# schematic.net
KiCad netlist of a schematic drawn in EAGLE
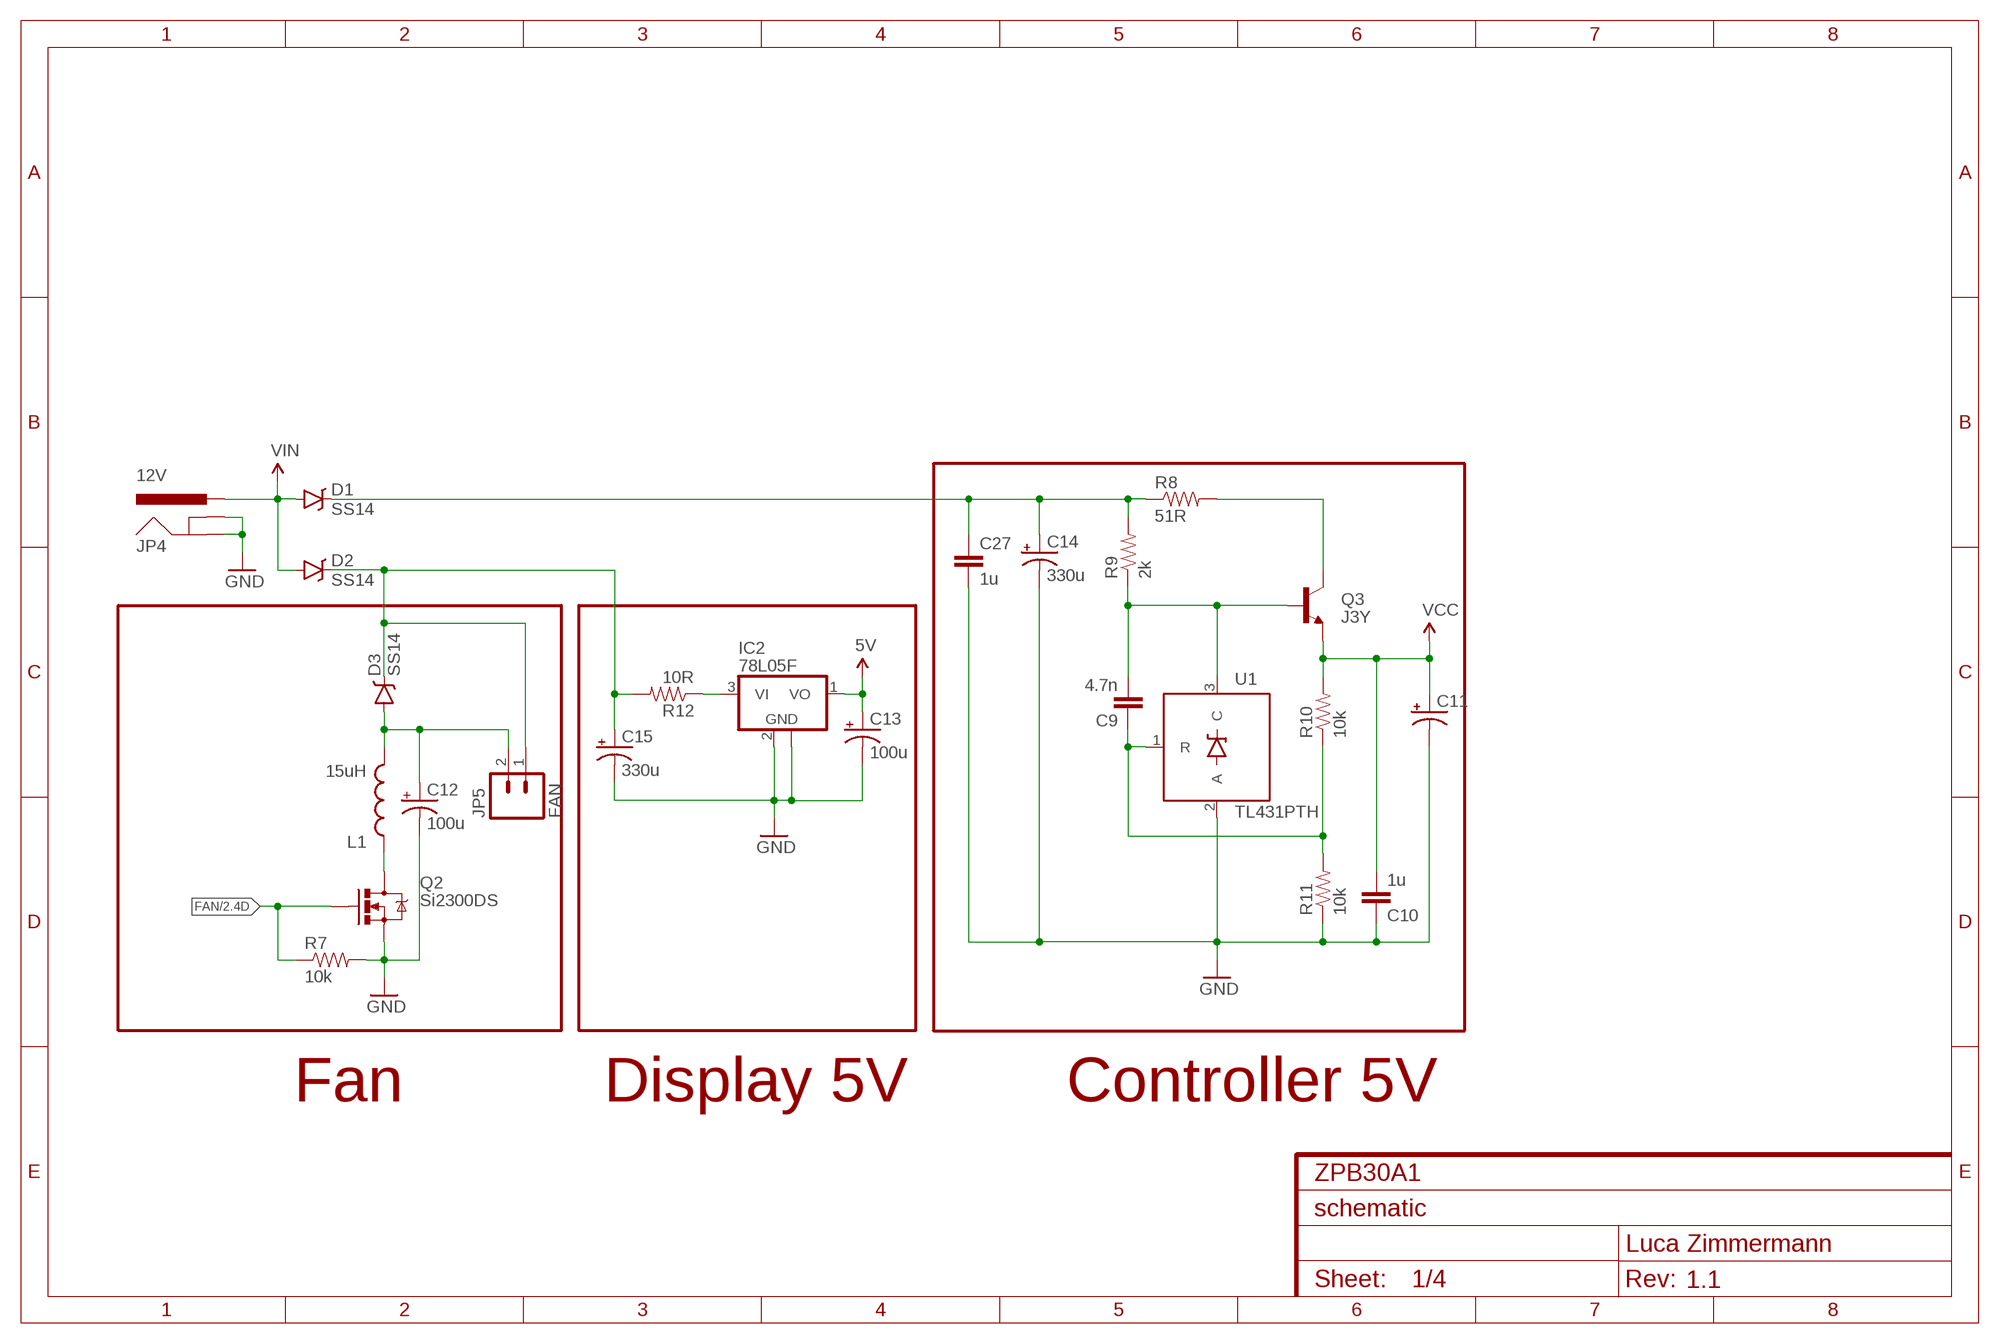
[diagram p0: schematic, sheet 1]
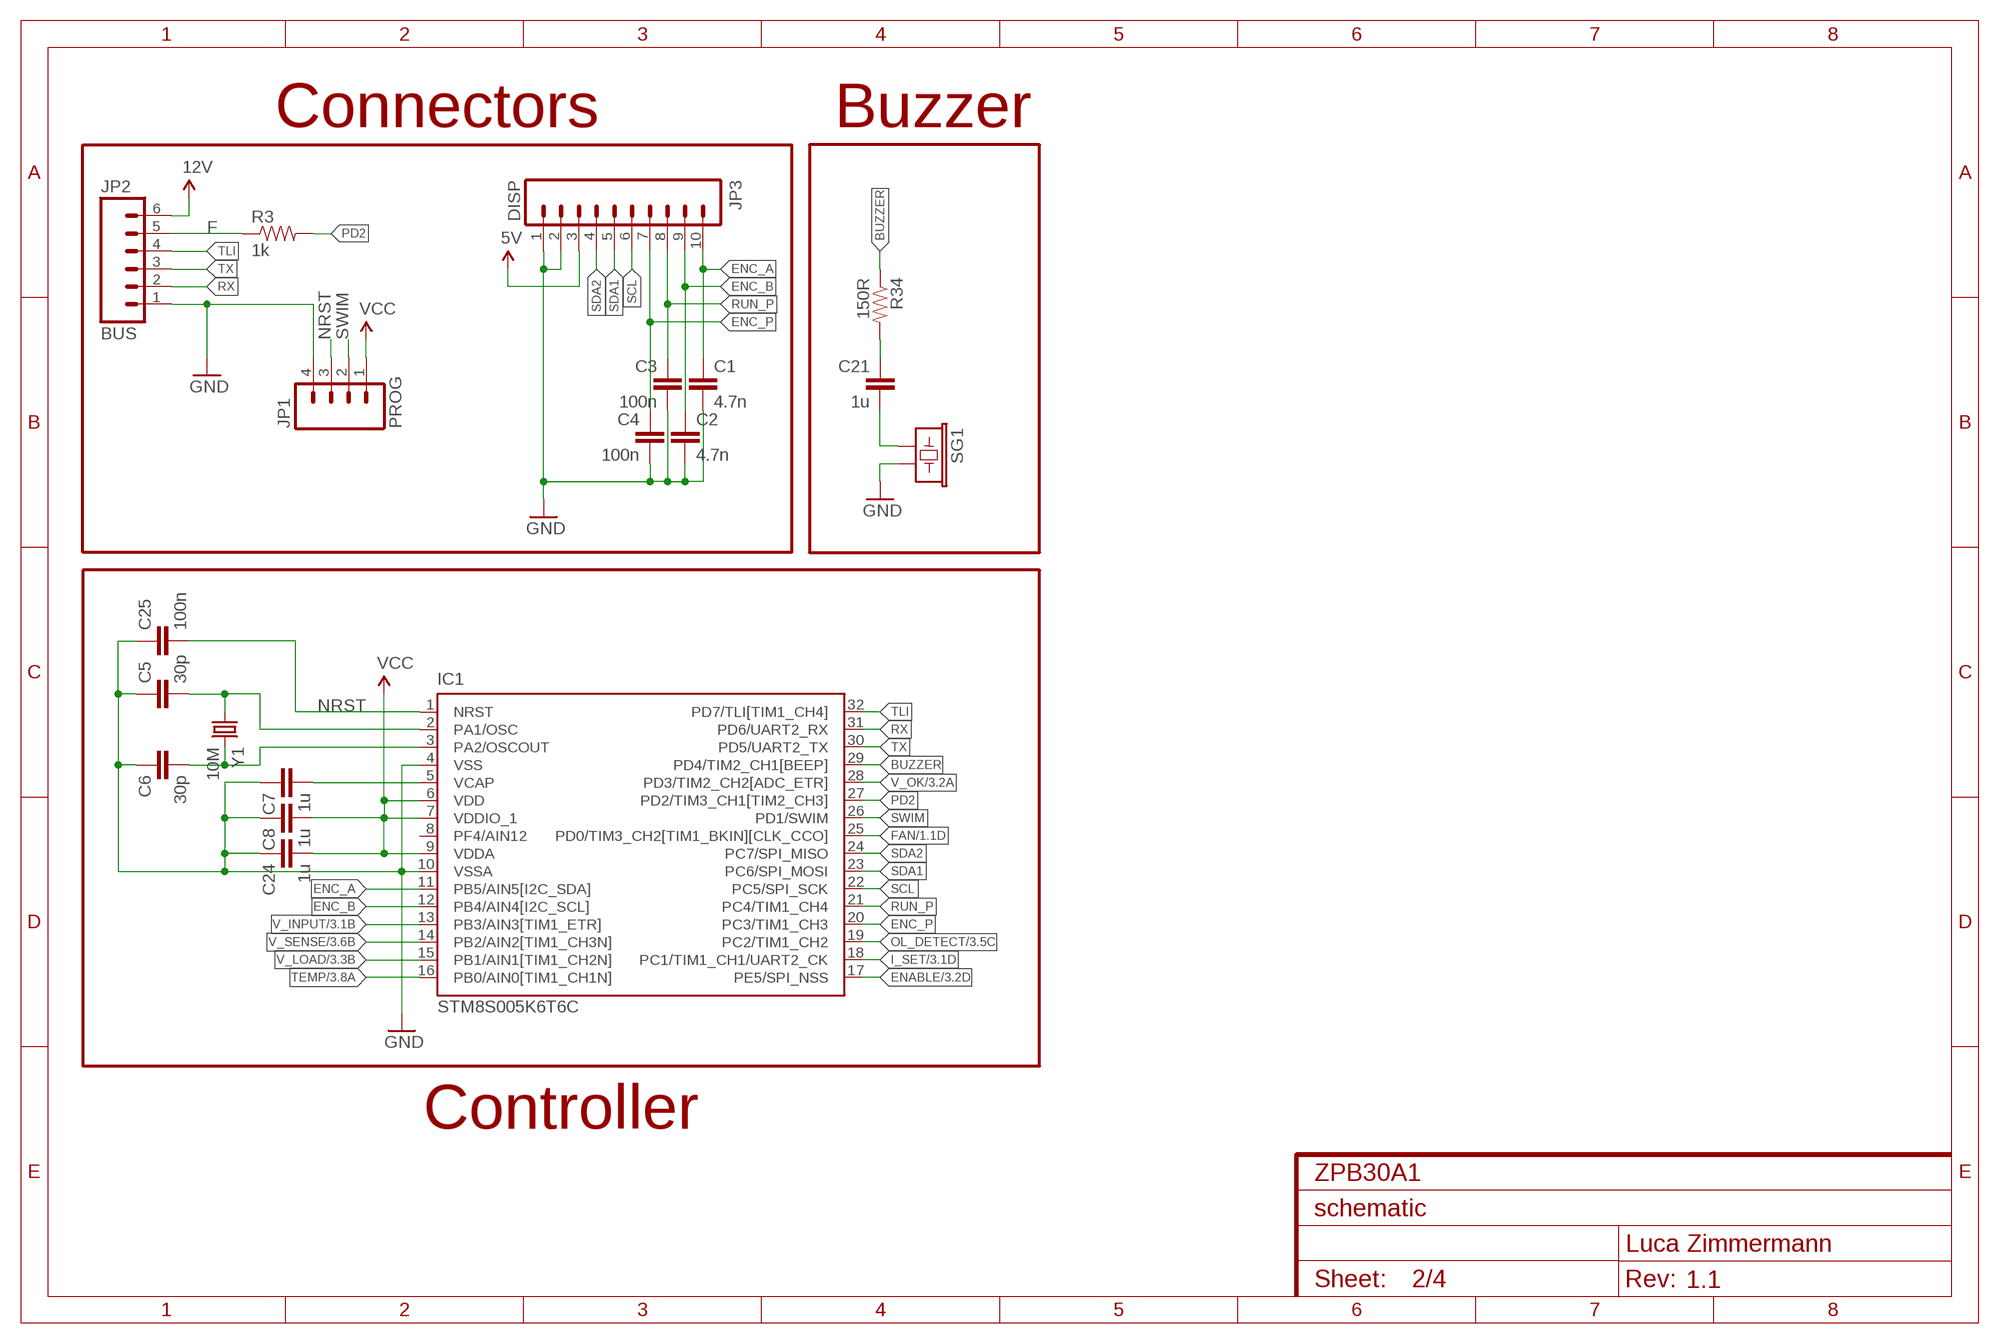
[diagram p1: schematic, sheet 2]
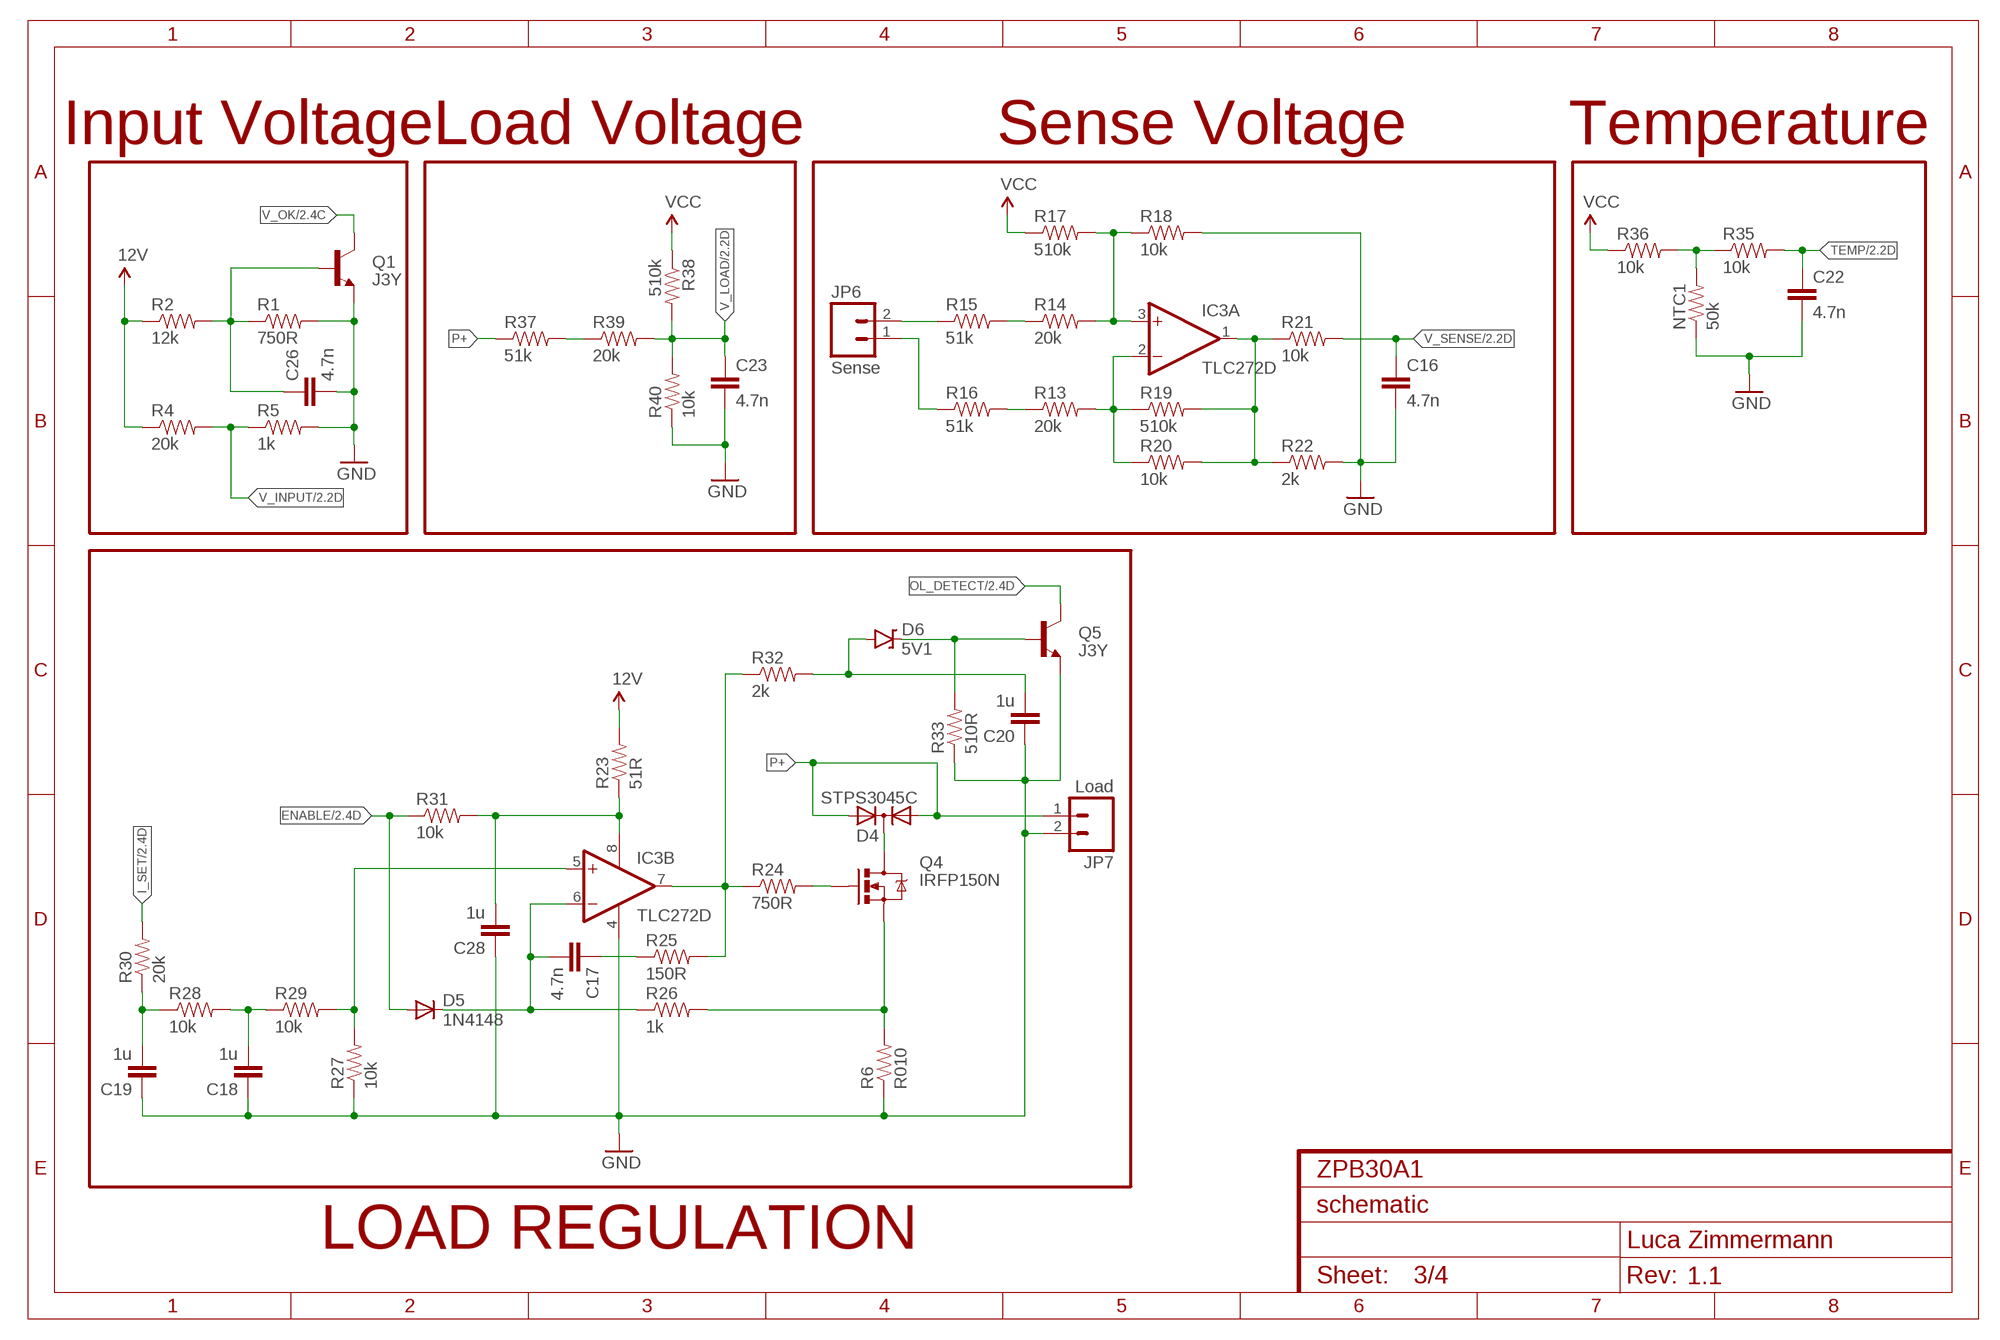
[diagram p2: schematic, sheet 3]
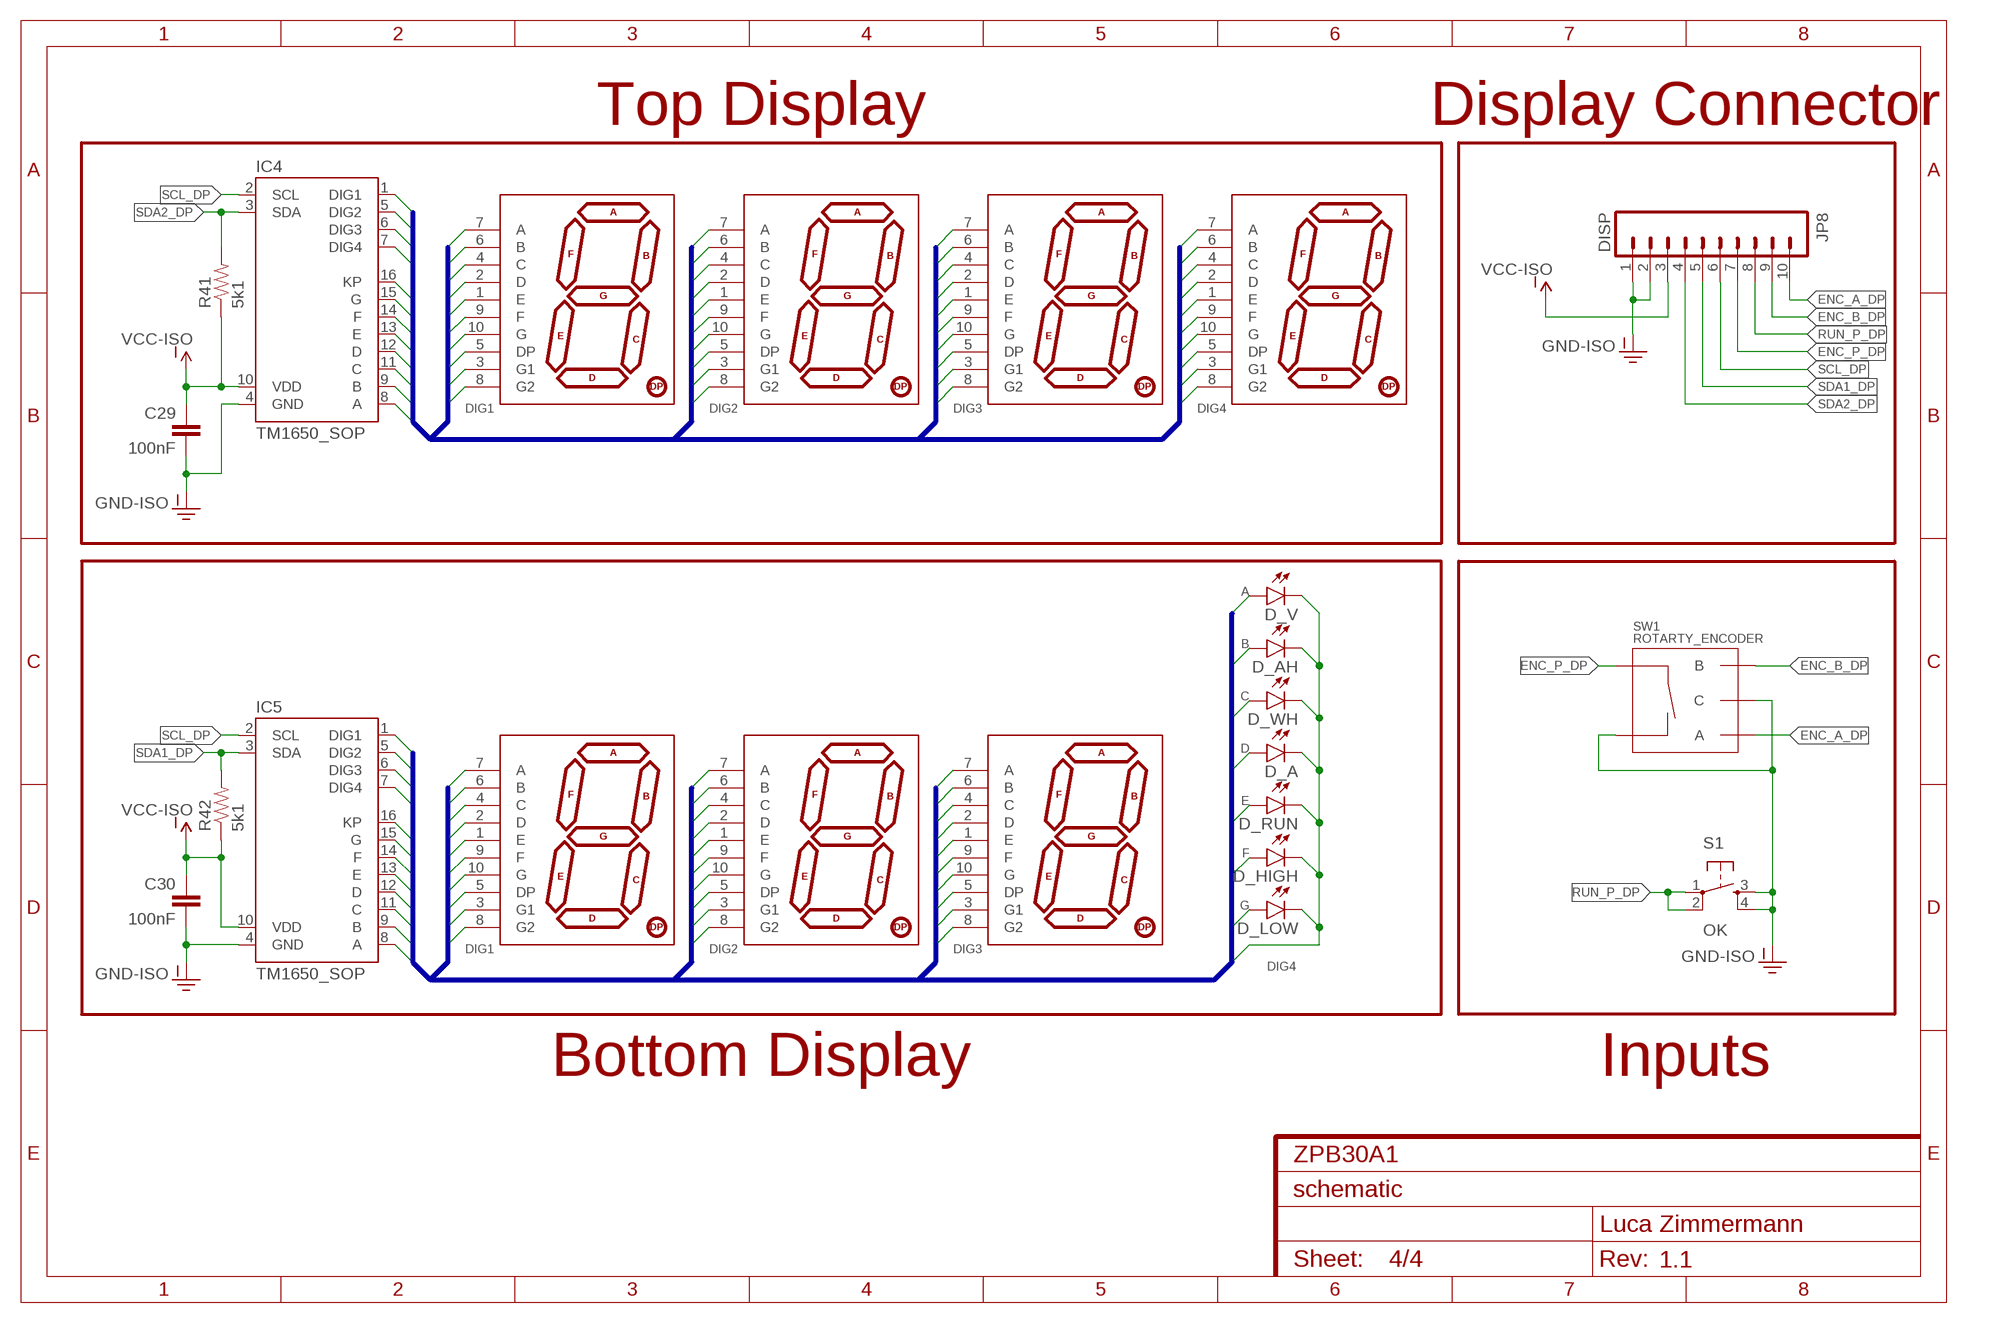
[diagram p3: schematic, sheet 4]

(export (version "E")
  (design (tool "Eeschema 10.0.6"))
  (components
    (comp (ref "C16")
      (value "4.7n")
      (footprint "eagle-import:C0805")
      (libsource (lib "eagle-import") (part "CAP0805"))
    )
    (comp (ref "C17")
      (value "4.7n")
      (footprint "eagle-import:C0805")
      (libsource (lib "eagle-import") (part "CAP0805"))
    )
    (comp (ref "C18")
      (value "1u")
      (footprint "eagle-import:C0805")
      (libsource (lib "eagle-import") (part "CAP0805"))
    )
    (comp (ref "C19")
      (value "1u")
      (footprint "eagle-import:C0805")
      (libsource (lib "eagle-import") (part "CAP0805"))
    )
    (comp (ref "C20")
      (value "1u")
      (footprint "eagle-import:C0805")
      (libsource (lib "eagle-import") (part "CAP0805"))
    )
    (comp (ref "C22")
      (value "4.7n")
      (footprint "eagle-import:C0805")
      (libsource (lib "eagle-import") (part "CAP0805"))
    )
    (comp (ref "C23")
      (value "4.7n")
      (footprint "eagle-import:C0805")
      (libsource (lib "eagle-import") (part "CAP0805"))
    )
    (comp (ref "C26")
      (value "4.7n")
      (footprint "eagle-import:C0805")
      (libsource (lib "eagle-import") (part "CAP0805"))
    )
    (comp (ref "C28")
      (value "1u")
      (footprint "eagle-import:C0805")
      (libsource (lib "eagle-import") (part "CAP0805"))
    )
    (comp (ref "D4")
      (value "STPS3045C")
      (footprint "eagle-import:TO220ABS")
      (libsource (lib "eagle-import") (part "FEP16AT"))
    )
    (comp (ref "D5")
      (value "1N4148")
      (footprint "eagle-import:MINIMELF")
      (libsource (lib "eagle-import") (part "DIODE-MINIMELF"))
    )
    (comp (ref "D6")
      (value "5V1")
      (footprint "eagle-import:SOD-123")
      (libsource (lib "eagle-import") (part "DIODE-ZENER16V"))
    )
    (comp (ref "IC3")
      (value "TLC272D")
      (footprint "eagle-import:SO08")
      (libsource (lib "eagle-import") (part "TLC272D"))
    )
    (comp (ref "JP6")
      (value "Sense")
      (footprint "eagle-import:JST-2-PTH-VERT")
      (libsource (lib "eagle-import") (part "M02JST-PTH-VERT"))
    )
    (comp (ref "JP7")
      (value "Load")
      (footprint "eagle-import:SCREWTERMINAL-5MM-2")
      (libsource (lib "eagle-import") (part "M025MM"))
    )
    (comp (ref "NTC1")
      (value "50k")
      (footprint "eagle-import:AXIAL-0.3")
      (libsource (lib "eagle-import") (part "RESISTORAXIAL-0.3"))
    )
    (comp (ref "Q1")
      (value "J3Y")
      (footprint "eagle-import:SOT23-3")
      (libsource (lib "eagle-import") (part "TRANSISTOR_NPNMMBT5088"))
    )
    (comp (ref "Q4")
      (value "IRFP150N")
      (footprint "eagle-import:TO220V")
      (libsource (lib "eagle-import") (part "MOSFET-NCHANNELFQP30N06L"))
    )
    (comp (ref "Q5")
      (value "J3Y")
      (footprint "eagle-import:SOT23-3")
      (libsource (lib "eagle-import") (part "TRANSISTOR_NPNMMBT5088"))
    )
    (comp (ref "R1")
      (value "750R")
      (footprint "eagle-import:R0805")
      (libsource (lib "eagle-import") (part "RESISTOR0805-RES"))
    )
    (comp (ref "R2")
      (value "12k")
      (footprint "eagle-import:R0805")
      (libsource (lib "eagle-import") (part "RESISTOR0805-RES"))
    )
    (comp (ref "R4")
      (value "20k")
      (footprint "eagle-import:R0805")
      (libsource (lib "eagle-import") (part "RESISTOR0805-RES"))
    )
    (comp (ref "R5")
      (value "1k")
      (footprint "eagle-import:R0805")
      (libsource (lib "eagle-import") (part "RESISTOR0805-RES"))
    )
    (comp (ref "R6")
      (value "R010")
      (footprint "eagle-import:AXIAL-0.6")
      (libsource (lib "eagle-import") (part "RESISTORPTH-1W"))
    )
    (comp (ref "R13")
      (value "20k")
      (footprint "eagle-import:R0805")
      (libsource (lib "eagle-import") (part "RESISTOR0805-RES"))
    )
    (comp (ref "R14")
      (value "20k")
      (footprint "eagle-import:R0805")
      (libsource (lib "eagle-import") (part "RESISTOR0805-RES"))
    )
    (comp (ref "R15")
      (value "51k")
      (footprint "eagle-import:R0805")
      (libsource (lib "eagle-import") (part "RESISTOR0805-RES"))
    )
    (comp (ref "R16")
      (value "51k")
      (footprint "eagle-import:R0805")
      (libsource (lib "eagle-import") (part "RESISTOR0805-RES"))
    )
    (comp (ref "R17")
      (value "510k")
      (footprint "eagle-import:R0805")
      (libsource (lib "eagle-import") (part "RESISTOR0805-RES"))
    )
    (comp (ref "R18")
      (value "10k")
      (footprint "eagle-import:R0805")
      (libsource (lib "eagle-import") (part "RESISTOR0805-RES"))
    )
    (comp (ref "R19")
      (value "510k")
      (footprint "eagle-import:R0805")
      (libsource (lib "eagle-import") (part "RESISTOR0805-RES"))
    )
    (comp (ref "R20")
      (value "10k")
      (footprint "eagle-import:R0805")
      (libsource (lib "eagle-import") (part "RESISTOR0805-RES"))
    )
    (comp (ref "R21")
      (value "10k")
      (footprint "eagle-import:R0805")
      (libsource (lib "eagle-import") (part "RESISTOR0805-RES"))
    )
    (comp (ref "R22")
      (value "2k")
      (footprint "eagle-import:R0805")
      (libsource (lib "eagle-import") (part "RESISTOR0805-RES"))
    )
    (comp (ref "R23")
      (value "51R")
      (footprint "eagle-import:R0805")
      (libsource (lib "eagle-import") (part "RESISTOR0805-RES"))
    )
    (comp (ref "R24")
      (value "750R")
      (footprint "eagle-import:R0805")
      (libsource (lib "eagle-import") (part "RESISTOR0805-RES"))
    )
    (comp (ref "R25")
      (value "150R")
      (footprint "eagle-import:R0805")
      (libsource (lib "eagle-import") (part "RESISTOR0805-RES"))
    )
    (comp (ref "R26")
      (value "1k")
      (footprint "eagle-import:R0805")
      (libsource (lib "eagle-import") (part "RESISTOR0805-RES"))
    )
    (comp (ref "R27")
      (value "10k")
      (footprint "eagle-import:R0805")
      (libsource (lib "eagle-import") (part "RESISTOR0805-RES"))
    )
    (comp (ref "R28")
      (value "10k")
      (footprint "eagle-import:R0805")
      (libsource (lib "eagle-import") (part "RESISTOR0805-RES"))
    )
    (comp (ref "R29")
      (value "10k")
      (footprint "eagle-import:R0805")
      (libsource (lib "eagle-import") (part "RESISTOR0805-RES"))
    )
    (comp (ref "R30")
      (value "20k")
      (footprint "eagle-import:R0805")
      (libsource (lib "eagle-import") (part "RESISTOR0805-RES"))
    )
    (comp (ref "R31")
      (value "10k")
      (footprint "eagle-import:R0805")
      (libsource (lib "eagle-import") (part "RESISTOR0805-RES"))
    )
    (comp (ref "R32")
      (value "2k")
      (footprint "eagle-import:R0805")
      (libsource (lib "eagle-import") (part "RESISTOR0805-RES"))
    )
    (comp (ref "R33")
      (value "510R")
      (footprint "eagle-import:R0805")
      (libsource (lib "eagle-import") (part "RESISTOR0805-RES"))
    )
    (comp (ref "R35")
      (value "10k")
      (footprint "eagle-import:R0805")
      (libsource (lib "eagle-import") (part "RESISTOR0805-RES"))
    )
    (comp (ref "R36")
      (value "10k")
      (footprint "eagle-import:R0805")
      (libsource (lib "eagle-import") (part "RESISTOR0805-RES"))
    )
    (comp (ref "R37")
      (value "51k")
      (footprint "eagle-import:R0805")
      (libsource (lib "eagle-import") (part "RESISTOR0805-RES"))
    )
    (comp (ref "R38")
      (value "510k")
      (footprint "eagle-import:R0805")
      (libsource (lib "eagle-import") (part "RESISTOR0805-RES"))
    )
    (comp (ref "R39")
      (value "20k")
      (footprint "eagle-import:R0805")
      (libsource (lib "eagle-import") (part "RESISTOR0805-RES"))
    )
    (comp (ref "R40")
      (value "10k")
      (footprint "eagle-import:R0805")
      (libsource (lib "eagle-import") (part "RESISTOR0805-RES"))
    )
    (comp (ref "C29")
      (value "100nF")
      (footprint "eagle-import:C0805")
      (libsource (lib "eagle-import") (part "CAP0805"))
    )
    (comp (ref "C30")
      (value "100nF")
      (footprint "eagle-import:C0805")
      (libsource (lib "eagle-import") (part "CAP0805"))
    )
    (comp (ref "DP1_DIG1")
      (value "7-SEGMENT-DISPLAY-1\"-RED")
      (footprint "eagle-import:7-SEGMENT-1_PTH")
      (libsource (lib "eagle-import") (part "7-SEGMENT-DISPLAY-1{dblquote}-RED"))
    )
    (comp (ref "DP1_DIG2")
      (value "7-SEGMENT-DISPLAY-1\"-RED")
      (footprint "eagle-import:7-SEGMENT-1_PTH")
      (libsource (lib "eagle-import") (part "7-SEGMENT-DISPLAY-1{dblquote}-RED"))
    )
    (comp (ref "DP1_DIG3")
      (value "7-SEGMENT-DISPLAY-1\"-RED")
      (footprint "eagle-import:7-SEGMENT-1_PTH")
      (libsource (lib "eagle-import") (part "7-SEGMENT-DISPLAY-1{dblquote}-RED"))
    )
    (comp (ref "DP1_DIG4")
      (value "7-SEGMENT-DISPLAY-1\"-RED")
      (footprint "eagle-import:7-SEGMENT-1_PTH")
      (libsource (lib "eagle-import") (part "7-SEGMENT-DISPLAY-1{dblquote}-RED"))
    )
    (comp (ref "DP2_DIG1")
      (value "7-SEGMENT-DISPLAY-1\"-RED")
      (footprint "eagle-import:7-SEGMENT-1_PTH")
      (libsource (lib "eagle-import") (part "7-SEGMENT-DISPLAY-1{dblquote}-RED"))
    )
    (comp (ref "DP2_DIG2")
      (value "7-SEGMENT-DISPLAY-1\"-RED")
      (footprint "eagle-import:7-SEGMENT-1_PTH")
      (libsource (lib "eagle-import") (part "7-SEGMENT-DISPLAY-1{dblquote}-RED"))
    )
    (comp (ref "DP2_DIG3")
      (value "7-SEGMENT-DISPLAY-1\"-RED")
      (footprint "eagle-import:7-SEGMENT-1_PTH")
      (libsource (lib "eagle-import") (part "7-SEGMENT-DISPLAY-1{dblquote}-RED"))
    )
    (comp (ref "D_A")
      (value "LED3MM")
      (footprint "eagle-import:LED3MM")
      (libsource (lib "eagle-import") (part "LED3MM"))
    )
    (comp (ref "D_AH")
      (value "LED3MM")
      (footprint "eagle-import:LED3MM")
      (libsource (lib "eagle-import") (part "LED3MM"))
    )
    (comp (ref "D_HIGH")
      (value "LED3MM")
      (footprint "eagle-import:LED3MM")
      (libsource (lib "eagle-import") (part "LED3MM"))
    )
    (comp (ref "D_LOW")
      (value "LED3MM")
      (footprint "eagle-import:LED3MM")
      (libsource (lib "eagle-import") (part "LED3MM"))
    )
    (comp (ref "D_RUN")
      (value "LED3MM")
      (footprint "eagle-import:LED3MM")
      (libsource (lib "eagle-import") (part "LED3MM"))
    )
    (comp (ref "D_V")
      (value "LED3MM")
      (footprint "eagle-import:LED3MM")
      (libsource (lib "eagle-import") (part "LED3MM"))
    )
    (comp (ref "D_WH")
      (value "LED3MM")
      (footprint "eagle-import:LED3MM")
      (libsource (lib "eagle-import") (part "LED3MM"))
    )
    (comp (ref "IC4")
      (value "TM1650_SOP")
      (footprint "eagle-import:SOP16")
      (libsource (lib "eagle-import") (part "TM1650_SOP"))
    )
    (comp (ref "IC5")
      (value "TM1650_SOP")
      (footprint "eagle-import:SOP16")
      (libsource (lib "eagle-import") (part "TM1650_SOP"))
    )
    (comp (ref "JP8")
      (value "DISP")
      (footprint "eagle-import:1X10")
      (libsource (lib "eagle-import") (part "M10SILK_FEMALE_PTH"))
    )
    (comp (ref "R41")
      (value "5k1")
      (footprint "eagle-import:R0805")
      (libsource (lib "eagle-import") (part "RESISTOR0805-RES"))
    )
    (comp (ref "R42")
      (value "5k1")
      (footprint "eagle-import:R0805")
      (libsource (lib "eagle-import") (part "RESISTOR0805-RES"))
    )
    (comp (ref "S1")
      (value "OK")
      (footprint "eagle-import:TACTILE-PTH")
      (libsource (lib "eagle-import") (part "SWITCH-MOMENTARY-4_PTH"))
    )
    (comp (ref "SW1")
      (value "ROTARTY_ENCODER")
      (footprint "eagle-import:ROTARY_ENC_PLAIN")
      (libsource (lib "eagle-import") (part "ROTARTY_ENCODER"))
    )
    (comp (ref "C1")
      (value "4.7n")
      (footprint "eagle-import:C0805")
      (libsource (lib "eagle-import") (part "CAP0805"))
    )
    (comp (ref "C2")
      (value "4.7n")
      (footprint "eagle-import:C0805")
      (libsource (lib "eagle-import") (part "CAP0805"))
    )
    (comp (ref "C3")
      (value "100n")
      (footprint "eagle-import:C0805")
      (libsource (lib "eagle-import") (part "CAP0805"))
    )
    (comp (ref "C4")
      (value "100n")
      (footprint "eagle-import:C0805")
      (libsource (lib "eagle-import") (part "CAP0805"))
    )
    (comp (ref "C5")
      (value "30p")
      (footprint "eagle-import:C0805")
      (libsource (lib "eagle-import") (part "CAP0805"))
    )
    (comp (ref "C6")
      (value "30p")
      (footprint "eagle-import:C0805")
      (libsource (lib "eagle-import") (part "CAP0805"))
    )
    (comp (ref "C7")
      (value "1u")
      (footprint "eagle-import:C0805")
      (libsource (lib "eagle-import") (part "CAP0805"))
    )
    (comp (ref "C8")
      (value "1u")
      (footprint "eagle-import:C0805")
      (libsource (lib "eagle-import") (part "CAP0805"))
    )
    (comp (ref "C21")
      (value "1u")
      (footprint "eagle-import:C0805")
      (libsource (lib "eagle-import") (part "CAP0805"))
    )
    (comp (ref "C24")
      (value "1u")
      (footprint "eagle-import:C0805")
      (libsource (lib "eagle-import") (part "CAP0805"))
    )
    (comp (ref "C25")
      (value "100n")
      (footprint "eagle-import:C0805")
      (libsource (lib "eagle-import") (part "CAP0805"))
    )
    (comp (ref "IC1")
      (value "STM8S005K6T6C")
      (footprint "eagle-import:LQFP32-7X7")
      (fields (field (name "MPN") "STM8S105K4T6C"))
      (libsource (lib "eagle-import") (part "STM8S105KT4"))
    )
    (comp (ref "JP1")
      (value "PROG")
      (footprint "eagle-import:1X04")
      (libsource (lib "eagle-import") (part "M04PTH"))
    )
    (comp (ref "JP2")
      (value "BUS")
      (footprint "eagle-import:1X06")
      (libsource (lib "eagle-import") (part "M06SILK_FEMALE_PTH"))
    )
    (comp (ref "JP3")
      (value "DISP")
      (footprint "eagle-import:1X10")
      (libsource (lib "eagle-import") (part "M10SILK_FEMALE_PTH"))
    )
    (comp (ref "R3")
      (value "1k")
      (footprint "eagle-import:R0805")
      (libsource (lib "eagle-import") (part "RESISTOR0805-RES"))
    )
    (comp (ref "R34")
      (value "150R")
      (footprint "eagle-import:R0805")
      (libsource (lib "eagle-import") (part "RESISTOR0805-RES"))
    )
    (comp (ref "SG1")
      (value "BUZZERPTH")
      (footprint "eagle-import:BUZZER-12MM")
      (libsource (lib "eagle-import") (part "BUZZERPTH"))
    )
    (comp (ref "Y1")
      (value "10M")
      (footprint "eagle-import:HC49UP")
      (libsource (lib "eagle-import") (part "CRYSTALSMD"))
    )
    (comp (ref "C9")
      (value "4.7n")
      (footprint "eagle-import:C0805")
      (libsource (lib "eagle-import") (part "CAP0805"))
    )
    (comp (ref "C10")
      (value "1u")
      (footprint "eagle-import:C0805")
      (libsource (lib "eagle-import") (part "CAP0805"))
    )
    (comp (ref "C11")
      (value "CAP_POLPTH2")
      (footprint "eagle-import:CPOL-RADIAL-10UF-25V")
      (libsource (lib "eagle-import") (part "CAP_POLPTH2"))
    )
    (comp (ref "C12")
      (value "100u")
      (footprint "eagle-import:CPOL-RADIAL-10UF-25V")
      (libsource (lib "eagle-import") (part "CAP_POLPTH2"))
    )
    (comp (ref "C13")
      (value "100u")
      (footprint "eagle-import:CPOL-RADIAL-10UF-25V")
      (libsource (lib "eagle-import") (part "CAP_POLPTH2"))
    )
    (comp (ref "C14")
      (value "330u")
      (footprint "eagle-import:CPOL-RADIAL-100UF-25V")
      (libsource (lib "eagle-import") (part "CAP_POLPTH1"))
    )
    (comp (ref "C15")
      (value "330u")
      (footprint "eagle-import:CPOL-RADIAL-100UF-25V")
      (libsource (lib "eagle-import") (part "CAP_POLPTH1"))
    )
    (comp (ref "C27")
      (value "1u")
      (footprint "eagle-import:C0805")
      (libsource (lib "eagle-import") (part "CAP0805"))
    )
    (comp (ref "D1")
      (value "SS14")
      (footprint "eagle-import:SMA-DIODE")
      (libsource (lib "eagle-import") (part "DIODE-SCHOTTKY-B340A"))
    )
    (comp (ref "D2")
      (value "SS14")
      (footprint "eagle-import:SMA-DIODE")
      (libsource (lib "eagle-import") (part "DIODE-SCHOTTKY-B340A"))
    )
    (comp (ref "D3")
      (value "SS14")
      (footprint "eagle-import:SMA-DIODE")
      (libsource (lib "eagle-import") (part "DIODE-SCHOTTKY-B340A"))
    )
    (comp (ref "IC2")
      (value "78L05F")
      (footprint "eagle-import:SOT89")
      (libsource (lib "eagle-import") (part "78LF05"))
    )
    (comp (ref "JP4")
      (value "12V")
      (footprint "eagle-import:POWER_JACK_SLOT")
      (libsource (lib "eagle-import") (part "POWER_JACKSLT"))
    )
    (comp (ref "JP5")
      (value "FAN")
      (footprint "eagle-import:1X02_XTRA_BIG")
      (libsource (lib "eagle-import") (part "M02PTH4"))
    )
    (comp (ref "L1")
      (value "15uH")
      (footprint "eagle-import:B82462G")
      (libsource (lib "eagle-import") (part "INDUCTOR-B82462G"))
    )
    (comp (ref "Q2")
      (value "Si2300DS")
      (footprint "eagle-import:SOT23-3")
      (libsource (lib "eagle-import") (part "MOSFET-NCHANNELAO3404A"))
    )
    (comp (ref "Q3")
      (value "J3Y")
      (footprint "eagle-import:SOT23-3")
      (libsource (lib "eagle-import") (part "TRANSISTOR_NPNMMBT5088"))
    )
    (comp (ref "R7")
      (value "10k")
      (footprint "eagle-import:R0805")
      (libsource (lib "eagle-import") (part "RESISTOR0805-RES"))
    )
    (comp (ref "R8")
      (value "51R")
      (footprint "eagle-import:R0805")
      (libsource (lib "eagle-import") (part "RESISTOR0805-RES"))
    )
    (comp (ref "R9")
      (value "2k")
      (footprint "eagle-import:R0805")
      (libsource (lib "eagle-import") (part "RESISTOR0805-RES"))
    )
    (comp (ref "R10")
      (value "10k")
      (footprint "eagle-import:R0805")
      (libsource (lib "eagle-import") (part "RESISTOR0805-RES"))
    )
    (comp (ref "R11")
      (value "10k")
      (footprint "eagle-import:R0805")
      (libsource (lib "eagle-import") (part "RESISTOR0805-RES"))
    )
    (comp (ref "R12")
      (value "10R")
      (footprint "eagle-import:R0805")
      (libsource (lib "eagle-import") (part "RESISTOR0805-RES"))
    )
    (comp (ref "U1")
      (value "TL431PTH")
      (footprint "eagle-import:TO-92")
      (libsource (lib "eagle-import") (part "TL431PTH"))
    )
  )
  (nets
    (net (code "1") (name "5V") (class "Default")
      (node (ref "C13") (pin "1") (pinfunction "+_1") (pintype "passive"))
      (node (ref "IC2") (pin "1") (pinfunction "VO_1") (pintype "passive"))
      (node (ref "JP3") (pin "3") (pinfunction "3_3") (pintype "passive"))
    )
    (net (code "2") (name "12V") (class "Default")
      (node (ref "JP2") (pin "6") (pinfunction "6_6") (pintype "passive"))
      (node (ref "R2") (pin "1") (pinfunction "1_1") (pintype "passive"))
      (node (ref "R23") (pin "2") (pinfunction "2_2") (pintype "passive"))
      (node (ref "R4") (pin "1") (pinfunction "1_1") (pintype "passive"))
    )
    (net (code "3") (name "BUZZER") (class "Default")
      (node (ref "IC1") (pin "29") (pinfunction "PD4/TIM2_CH1[BEEP]_29") (pintype "bidirectional"))
      (node (ref "R34") (pin "1") (pinfunction "1_1") (pintype "passive"))
    )
    (net (code "4") (name "DP1") (class "Default")
      (node (ref "DP1_DIG1") (pin "1") (pinfunction "E_1") (pintype "bidirectional"))
      (node (ref "DP1_DIG1") (pin "10") (pinfunction "G_10") (pintype "bidirectional"))
      (node (ref "DP1_DIG1") (pin "2") (pinfunction "D_2") (pintype "bidirectional"))
      (node (ref "DP1_DIG1") (pin "3") (pinfunction "G1_3") (pintype "bidirectional"))
      (node (ref "DP1_DIG1") (pin "4") (pinfunction "C_4") (pintype "bidirectional"))
      (node (ref "DP1_DIG1") (pin "5") (pinfunction "DP_5") (pintype "bidirectional"))
      (node (ref "DP1_DIG1") (pin "6") (pinfunction "B_6") (pintype "bidirectional"))
      (node (ref "DP1_DIG1") (pin "7") (pinfunction "A_7") (pintype "bidirectional"))
      (node (ref "DP1_DIG1") (pin "8") (pinfunction "G2_8") (pintype "bidirectional"))
      (node (ref "DP1_DIG1") (pin "9") (pinfunction "F_9") (pintype "bidirectional"))
      (node (ref "DP1_DIG2") (pin "1") (pinfunction "E_1") (pintype "bidirectional"))
      (node (ref "DP1_DIG2") (pin "10") (pinfunction "G_10") (pintype "bidirectional"))
      (node (ref "DP1_DIG2") (pin "2") (pinfunction "D_2") (pintype "bidirectional"))
      (node (ref "DP1_DIG2") (pin "3") (pinfunction "G1_3") (pintype "bidirectional"))
      (node (ref "DP1_DIG2") (pin "4") (pinfunction "C_4") (pintype "bidirectional"))
      (node (ref "DP1_DIG2") (pin "5") (pinfunction "DP_5") (pintype "bidirectional"))
      (node (ref "DP1_DIG2") (pin "6") (pinfunction "B_6") (pintype "bidirectional"))
      (node (ref "DP1_DIG2") (pin "7") (pinfunction "A_7") (pintype "bidirectional"))
      (node (ref "DP1_DIG2") (pin "8") (pinfunction "G2_8") (pintype "bidirectional"))
      (node (ref "DP1_DIG2") (pin "9") (pinfunction "F_9") (pintype "bidirectional"))
      (node (ref "DP1_DIG3") (pin "1") (pinfunction "E_1") (pintype "bidirectional"))
      (node (ref "DP1_DIG3") (pin "10") (pinfunction "G_10") (pintype "bidirectional"))
      (node (ref "DP1_DIG3") (pin "2") (pinfunction "D_2") (pintype "bidirectional"))
      (node (ref "DP1_DIG3") (pin "3") (pinfunction "G1_3") (pintype "bidirectional"))
      (node (ref "DP1_DIG3") (pin "4") (pinfunction "C_4") (pintype "bidirectional"))
      (node (ref "DP1_DIG3") (pin "5") (pinfunction "DP_5") (pintype "bidirectional"))
      (node (ref "DP1_DIG3") (pin "6") (pinfunction "B_6") (pintype "bidirectional"))
      (node (ref "DP1_DIG3") (pin "7") (pinfunction "A_7") (pintype "bidirectional"))
      (node (ref "DP1_DIG3") (pin "8") (pinfunction "G2_8") (pintype "bidirectional"))
      (node (ref "DP1_DIG3") (pin "9") (pinfunction "F_9") (pintype "bidirectional"))
      (node (ref "DP1_DIG4") (pin "1") (pinfunction "E_1") (pintype "bidirectional"))
      (node (ref "DP1_DIG4") (pin "10") (pinfunction "G_10") (pintype "bidirectional"))
      (node (ref "DP1_DIG4") (pin "2") (pinfunction "D_2") (pintype "bidirectional"))
      (node (ref "DP1_DIG4") (pin "3") (pinfunction "G1_3") (pintype "bidirectional"))
      (node (ref "DP1_DIG4") (pin "4") (pinfunction "C_4") (pintype "bidirectional"))
      (node (ref "DP1_DIG4") (pin "5") (pinfunction "DP_5") (pintype "bidirectional"))
      (node (ref "DP1_DIG4") (pin "6") (pinfunction "B_6") (pintype "bidirectional"))
      (node (ref "DP1_DIG4") (pin "7") (pinfunction "A_7") (pintype "bidirectional"))
      (node (ref "DP1_DIG4") (pin "8") (pinfunction "G2_8") (pintype "bidirectional"))
      (node (ref "DP1_DIG4") (pin "9") (pinfunction "F_9") (pintype "bidirectional"))
      (node (ref "IC4") (pin "1") (pinfunction "DIG1_1") (pintype "output"))
      (node (ref "IC4") (pin "11") (pinfunction "C_11") (pintype "open_collector"))
      (node (ref "IC4") (pin "12") (pinfunction "D_12") (pintype "open_collector"))
      (node (ref "IC4") (pin "13") (pinfunction "E_13") (pintype "open_collector"))
      (node (ref "IC4") (pin "14") (pinfunction "F_14") (pintype "open_collector"))
      (node (ref "IC4") (pin "15") (pinfunction "G_15") (pintype "open_collector"))
      (node (ref "IC4") (pin "16") (pinfunction "KP_16") (pintype "open_collector"))
      (node (ref "IC4") (pin "5") (pinfunction "DIG2_5") (pintype "output"))
      (node (ref "IC4") (pin "6") (pinfunction "DIG3_6") (pintype "output"))
      (node (ref "IC4") (pin "7") (pinfunction "DIG4_7") (pintype "output"))
      (node (ref "IC4") (pin "8") (pinfunction "A_8") (pintype "open_collector"))
      (node (ref "IC4") (pin "9") (pinfunction "B_9") (pintype "open_collector"))
    )
    (net (code "5") (name "DP2") (class "Default")
      (node (ref "DP2_DIG1") (pin "1") (pinfunction "E_1") (pintype "bidirectional"))
      (node (ref "DP2_DIG1") (pin "10") (pinfunction "G_10") (pintype "bidirectional"))
      (node (ref "DP2_DIG1") (pin "2") (pinfunction "D_2") (pintype "bidirectional"))
      (node (ref "DP2_DIG1") (pin "3") (pinfunction "G1_3") (pintype "bidirectional"))
      (node (ref "DP2_DIG1") (pin "4") (pinfunction "C_4") (pintype "bidirectional"))
      (node (ref "DP2_DIG1") (pin "5") (pinfunction "DP_5") (pintype "bidirectional"))
      (node (ref "DP2_DIG1") (pin "6") (pinfunction "B_6") (pintype "bidirectional"))
      (node (ref "DP2_DIG1") (pin "7") (pinfunction "A_7") (pintype "bidirectional"))
      (node (ref "DP2_DIG1") (pin "8") (pinfunction "G2_8") (pintype "bidirectional"))
      (node (ref "DP2_DIG1") (pin "9") (pinfunction "F_9") (pintype "bidirectional"))
      (node (ref "DP2_DIG2") (pin "1") (pinfunction "E_1") (pintype "bidirectional"))
      (node (ref "DP2_DIG2") (pin "10") (pinfunction "G_10") (pintype "bidirectional"))
      (node (ref "DP2_DIG2") (pin "2") (pinfunction "D_2") (pintype "bidirectional"))
      (node (ref "DP2_DIG2") (pin "3") (pinfunction "G1_3") (pintype "bidirectional"))
      (node (ref "DP2_DIG2") (pin "4") (pinfunction "C_4") (pintype "bidirectional"))
      (node (ref "DP2_DIG2") (pin "5") (pinfunction "DP_5") (pintype "bidirectional"))
      (node (ref "DP2_DIG2") (pin "6") (pinfunction "B_6") (pintype "bidirectional"))
      (node (ref "DP2_DIG2") (pin "7") (pinfunction "A_7") (pintype "bidirectional"))
      (node (ref "DP2_DIG2") (pin "8") (pinfunction "G2_8") (pintype "bidirectional"))
      (node (ref "DP2_DIG2") (pin "9") (pinfunction "F_9") (pintype "bidirectional"))
      (node (ref "DP2_DIG3") (pin "1") (pinfunction "E_1") (pintype "bidirectional"))
      (node (ref "DP2_DIG3") (pin "10") (pinfunction "G_10") (pintype "bidirectional"))
      (node (ref "DP2_DIG3") (pin "2") (pinfunction "D_2") (pintype "bidirectional"))
      (node (ref "DP2_DIG3") (pin "3") (pinfunction "G1_3") (pintype "bidirectional"))
      (node (ref "DP2_DIG3") (pin "4") (pinfunction "C_4") (pintype "bidirectional"))
      (node (ref "DP2_DIG3") (pin "5") (pinfunction "DP_5") (pintype "bidirectional"))
      (node (ref "DP2_DIG3") (pin "6") (pinfunction "B_6") (pintype "bidirectional"))
      (node (ref "DP2_DIG3") (pin "7") (pinfunction "A_7") (pintype "bidirectional"))
      (node (ref "DP2_DIG3") (pin "8") (pinfunction "G2_8") (pintype "bidirectional"))
      (node (ref "DP2_DIG3") (pin "9") (pinfunction "F_9") (pintype "bidirectional"))
      (node (ref "D_A") (pin "A") (pinfunction "A_A") (pintype "passive"))
      (node (ref "D_A") (pin "K") (pinfunction "C_K") (pintype "passive"))
      (node (ref "D_AH") (pin "A") (pinfunction "A_A") (pintype "passive"))
      (node (ref "D_AH") (pin "K") (pinfunction "C_K") (pintype "passive"))
      (node (ref "D_HIGH") (pin "A") (pinfunction "A_A") (pintype "passive"))
      (node (ref "D_HIGH") (pin "K") (pinfunction "C_K") (pintype "passive"))
      (node (ref "D_LOW") (pin "A") (pinfunction "A_A") (pintype "passive"))
      (node (ref "D_LOW") (pin "K") (pinfunction "C_K") (pintype "passive"))
      (node (ref "D_RUN") (pin "A") (pinfunction "A_A") (pintype "passive"))
      (node (ref "D_RUN") (pin "K") (pinfunction "C_K") (pintype "passive"))
      (node (ref "D_V") (pin "A") (pinfunction "A_A") (pintype "passive"))
      (node (ref "D_V") (pin "K") (pinfunction "C_K") (pintype "passive"))
      (node (ref "D_WH") (pin "A") (pinfunction "A_A") (pintype "passive"))
      (node (ref "D_WH") (pin "K") (pinfunction "C_K") (pintype "passive"))
      (node (ref "IC5") (pin "1") (pinfunction "DIG1_1") (pintype "output"))
      (node (ref "IC5") (pin "11") (pinfunction "C_11") (pintype "open_collector"))
      (node (ref "IC5") (pin "12") (pinfunction "D_12") (pintype "open_collector"))
      (node (ref "IC5") (pin "13") (pinfunction "E_13") (pintype "open_collector"))
      (node (ref "IC5") (pin "14") (pinfunction "F_14") (pintype "open_collector"))
      (node (ref "IC5") (pin "15") (pinfunction "G_15") (pintype "open_collector"))
      (node (ref "IC5") (pin "16") (pinfunction "KP_16") (pintype "open_collector"))
      (node (ref "IC5") (pin "5") (pinfunction "DIG2_5") (pintype "output"))
      (node (ref "IC5") (pin "6") (pinfunction "DIG3_6") (pintype "output"))
      (node (ref "IC5") (pin "7") (pinfunction "DIG4_7") (pintype "output"))
      (node (ref "IC5") (pin "8") (pinfunction "A_8") (pintype "open_collector"))
      (node (ref "IC5") (pin "9") (pinfunction "B_9") (pintype "open_collector"))
    )
    (net (code "6") (name "ENABLE") (class "Default")
      (node (ref "D5") (pin "A") (pinfunction "A_A") (pintype "passive"))
      (node (ref "IC1") (pin "17") (pinfunction "PE5/SPI_NSS_17") (pintype "bidirectional"))
      (node (ref "R31") (pin "1") (pinfunction "1_1") (pintype "passive"))
    )
    (net (code "7") (name "ENC_A") (class "Default")
      (node (ref "C1") (pin "1") (pinfunction "1_1") (pintype "passive"))
      (node (ref "IC1") (pin "11") (pinfunction "PB5/AIN5[I2C_SDA]_11") (pintype "bidirectional"))
      (node (ref "JP3") (pin "10") (pinfunction "10_10") (pintype "passive"))
    )
    (net (code "8") (name "ENC_A_DP") (class "Default")
      (node (ref "JP8") (pin "10") (pinfunction "10_10") (pintype "passive"))
      (node (ref "SW1") (pin "A") (pinfunction "A_A") (pintype "bidirectional"))
    )
    (net (code "9") (name "ENC_B") (class "Default")
      (node (ref "C2") (pin "1") (pinfunction "1_1") (pintype "passive"))
      (node (ref "IC1") (pin "12") (pinfunction "PB4/AIN4[I2C_SCL]_12") (pintype "bidirectional"))
      (node (ref "JP3") (pin "9") (pinfunction "9_9") (pintype "passive"))
    )
    (net (code "10") (name "ENC_B_DP") (class "Default")
      (node (ref "JP8") (pin "9") (pinfunction "9_9") (pintype "passive"))
      (node (ref "SW1") (pin "B") (pinfunction "B_B") (pintype "bidirectional"))
    )
    (net (code "11") (name "ENC_P") (class "Default")
      (node (ref "C4") (pin "1") (pinfunction "1_1") (pintype "passive"))
      (node (ref "IC1") (pin "20") (pinfunction "PC3/TIM1_CH3_20") (pintype "bidirectional"))
      (node (ref "JP3") (pin "7") (pinfunction "7_7") (pintype "passive"))
    )
    (net (code "12") (name "ENC_P_DP") (class "Default")
      (node (ref "JP8") (pin "7") (pinfunction "7_7") (pintype "passive"))
      (node (ref "SW1") (pin "SW+") (pinfunction "SW+_SW+") (pintype "bidirectional"))
    )
    (net (code "13") (name "F") (class "Default")
      (node (ref "JP2") (pin "5") (pinfunction "5_5") (pintype "passive"))
      (node (ref "R3") (pin "1") (pinfunction "1_1") (pintype "passive"))
    )
    (net (code "14") (name "FAN") (class "Default")
      (node (ref "IC1") (pin "25") (pinfunction "PD0/TIM3_CH2[TIM1_BKIN][CLK_CCO]_25") (pintype "bidirectional"))
      (node (ref "Q2") (pin "1") (pinfunction "G_1") (pintype "passive"))
      (node (ref "R7") (pin "1") (pinfunction "1_1") (pintype "passive"))
    )
    (net (code "15") (name "GND") (class "Default")
      (node (ref "C1") (pin "2") (pinfunction "2_2") (pintype "passive"))
      (node (ref "C10") (pin "1") (pinfunction "1_1") (pintype "passive"))
      (node (ref "C11") (pin "2") (pinfunction "-_2") (pintype "passive"))
      (node (ref "C12") (pin "2") (pinfunction "-_2") (pintype "passive"))
      (node (ref "C13") (pin "2") (pinfunction "-_2") (pintype "passive"))
      (node (ref "C14") (pin "2") (pinfunction "-_2") (pintype "passive"))
      (node (ref "C15") (pin "2") (pinfunction "-_2") (pintype "passive"))
      (node (ref "C16") (pin "2") (pinfunction "2_2") (pintype "passive"))
      (node (ref "C18") (pin "1") (pinfunction "1_1") (pintype "passive"))
      (node (ref "C19") (pin "1") (pinfunction "1_1") (pintype "passive"))
      (node (ref "C2") (pin "2") (pinfunction "2_2") (pintype "passive"))
      (node (ref "C20") (pin "1") (pinfunction "1_1") (pintype "passive"))
      (node (ref "C22") (pin "2") (pinfunction "2_2") (pintype "passive"))
      (node (ref "C23") (pin "2") (pinfunction "2_2") (pintype "passive"))
      (node (ref "C24") (pin "1") (pinfunction "1_1") (pintype "passive"))
      (node (ref "C25") (pin "1") (pinfunction "1_1") (pintype "passive"))
      (node (ref "C26") (pin "2") (pinfunction "2_2") (pintype "passive"))
      (node (ref "C27") (pin "2") (pinfunction "2_2") (pintype "passive"))
      (node (ref "C28") (pin "1") (pinfunction "1_1") (pintype "passive"))
      (node (ref "C3") (pin "2") (pinfunction "2_2") (pintype "passive"))
      (node (ref "C4") (pin "2") (pinfunction "2_2") (pintype "passive"))
      (node (ref "C5") (pin "1") (pinfunction "1_1") (pintype "passive"))
      (node (ref "C6") (pin "1") (pinfunction "1_1") (pintype "passive"))
      (node (ref "C7") (pin "1") (pinfunction "1_1") (pintype "passive"))
      (node (ref "C8") (pin "1") (pinfunction "1_1") (pintype "passive"))
      (node (ref "IC1") (pin "10") (pinfunction "VSSA_10") (pintype "power_in"))
      (node (ref "IC1") (pin "4") (pinfunction "VSS_4") (pintype "power_in"))
      (node (ref "IC2") (pin "2") (pinfunction "GND_2") (pintype "passive"))
      (node (ref "IC2") (pin "2@1") (pinfunction "GND_2@1") (pintype "passive"))
      (node (ref "IC3") (pin "4") (pinfunction "V-_4") (pintype "power_in"))
      (node (ref "JP1") (pin "4") (pinfunction "4_4") (pintype "passive"))
      (node (ref "JP2") (pin "1") (pinfunction "1_1") (pintype "passive"))
      (node (ref "JP3") (pin "1") (pinfunction "1_1") (pintype "passive"))
      (node (ref "JP3") (pin "2") (pinfunction "2_2") (pintype "passive"))
      (node (ref "JP4") (pin "GND@1") (pinfunction "GNDBREAK_GND@1") (pintype "bidirectional"))
      (node (ref "JP4") (pin "GND@2") (pinfunction "GND_GND@2") (pintype "bidirectional"))
      (node (ref "JP7") (pin "2") (pinfunction "2_2") (pintype "passive"))
      (node (ref "NTC1") (pin "P$1") (pinfunction "1_P$1") (pintype "passive"))
      (node (ref "Q1") (pin "2") (pinfunction "E_2") (pintype "passive"))
      (node (ref "Q2") (pin "2") (pinfunction "S_2") (pintype "passive"))
      (node (ref "Q5") (pin "2") (pinfunction "E_2") (pintype "passive"))
      (node (ref "R1") (pin "2") (pinfunction "2_2") (pintype "passive"))
      (node (ref "R11") (pin "1") (pinfunction "1_1") (pintype "passive"))
      (node (ref "R18") (pin "2") (pinfunction "2_2") (pintype "passive"))
      (node (ref "R22") (pin "2") (pinfunction "2_2") (pintype "passive"))
      (node (ref "R27") (pin "1") (pinfunction "1_1") (pintype "passive"))
      (node (ref "R33") (pin "1") (pinfunction "1_1") (pintype "passive"))
      (node (ref "R40") (pin "1") (pinfunction "1_1") (pintype "passive"))
      (node (ref "R5") (pin "2") (pinfunction "2_2") (pintype "passive"))
      (node (ref "R6") (pin "P$1") (pinfunction "1_P$1") (pintype "passive"))
      (node (ref "R7") (pin "2") (pinfunction "2_2") (pintype "passive"))
      (node (ref "SG1") (pin "-") (pinfunction "2_-") (pintype "passive"))
      (node (ref "U1") (pin "2") (pinfunction "A_2") (pintype "bidirectional"))
    )
    (net (code "16") (name "GND-ISO") (class "Default")
      (node (ref "C29") (pin "2") (pinfunction "2_2") (pintype "passive"))
      (node (ref "C30") (pin "2") (pinfunction "2_2") (pintype "passive"))
      (node (ref "IC4") (pin "4") (pinfunction "GND_4") (pintype "power_in"))
      (node (ref "IC5") (pin "4") (pinfunction "GND_4") (pintype "power_in"))
      (node (ref "JP8") (pin "1") (pinfunction "1_1") (pintype "passive"))
      (node (ref "JP8") (pin "2") (pinfunction "2_2") (pintype "passive"))
      (node (ref "S1") (pin "3") (pinfunction "3_3") (pintype "passive"))
      (node (ref "S1") (pin "4") (pinfunction "4_4") (pintype "passive"))
      (node (ref "SW1") (pin "C") (pinfunction "C_C") (pintype "bidirectional"))
      (node (ref "SW1") (pin "SW-") (pinfunction "SW-_SW-") (pintype "bidirectional"))
    )
    (net (code "17") (name "I_SET") (class "Default")
      (node (ref "IC1") (pin "18") (pinfunction "PC1/TIM1_CH1/UART2_CK_18") (pintype "bidirectional"))
      (node (ref "R30") (pin "2") (pinfunction "2_2") (pintype "passive"))
    )
    (net (code "18") (name "NRST") (class "Default")
      (node (ref "C25") (pin "2") (pinfunction "2_2") (pintype "passive"))
      (node (ref "IC1") (pin "1") (pinfunction "NRST_1") (pintype "bidirectional"))
      (node (ref "JP1") (pin "3") (pinfunction "3_3") (pintype "passive"))
    )
    (net (code "19") (name "Net-(C12-+)") (class "Default")
      (node (ref "C12") (pin "1") (pinfunction "+_1") (pintype "passive"))
      (node (ref "D3") (pin "A") (pinfunction "A_A") (pintype "passive"))
      (node (ref "JP5") (pin "2") (pinfunction "2_2") (pintype "passive"))
      (node (ref "L1") (pin "P$2") (pinfunction "2_P$2") (pintype "passive"))
    )
    (net (code "20") (name "Net-(C14-+)") (class "Default")
      (node (ref "C14") (pin "1") (pinfunction "+_1") (pintype "passive"))
      (node (ref "C27") (pin "1") (pinfunction "1_1") (pintype "passive"))
      (node (ref "D1") (pin "C") (pinfunction "C_C") (pintype "passive"))
      (node (ref "R8") (pin "1") (pinfunction "1_1") (pintype "passive"))
      (node (ref "R9") (pin "2") (pinfunction "2_2") (pintype "passive"))
    )
    (net (code "21") (name "Net-(C15-+)") (class "Default")
      (node (ref "C15") (pin "1") (pinfunction "+_1") (pintype "passive"))
      (node (ref "D2") (pin "C") (pinfunction "C_C") (pintype "passive"))
      (node (ref "D3") (pin "C") (pinfunction "C_C") (pintype "passive"))
      (node (ref "JP5") (pin "1") (pinfunction "1_1") (pintype "passive"))
      (node (ref "R12") (pin "2") (pinfunction "2_2") (pintype "passive"))
    )
    (net (code "22") (name "Net-(C17-Pad1)") (class "Default")
      (node (ref "C17") (pin "1") (pinfunction "1_1") (pintype "passive"))
      (node (ref "R25") (pin "1") (pinfunction "1_1") (pintype "passive"))
    )
    (net (code "23") (name "Net-(C18-Pad2)") (class "Default")
      (node (ref "C18") (pin "2") (pinfunction "2_2") (pintype "passive"))
      (node (ref "R28") (pin "2") (pinfunction "2_2") (pintype "passive"))
      (node (ref "R29") (pin "1") (pinfunction "1_1") (pintype "passive"))
    )
    (net (code "24") (name "Net-(C19-Pad2)") (class "Default")
      (node (ref "C19") (pin "2") (pinfunction "2_2") (pintype "passive"))
      (node (ref "R28") (pin "1") (pinfunction "1_1") (pintype "passive"))
      (node (ref "R30") (pin "1") (pinfunction "1_1") (pintype "passive"))
    )
    (net (code "25") (name "Net-(C20-Pad2)") (class "Default")
      (node (ref "C20") (pin "2") (pinfunction "2_2") (pintype "passive"))
      (node (ref "D6") (pin "A") (pinfunction "A_A") (pintype "passive"))
      (node (ref "R32") (pin "2") (pinfunction "2_2") (pintype "passive"))
    )
    (net (code "26") (name "Net-(C21-Pad1)") (class "Default")
      (node (ref "C21") (pin "1") (pinfunction "1_1") (pintype "passive"))
      (node (ref "R34") (pin "2") (pinfunction "2_2") (pintype "passive"))
    )
    (net (code "27") (name "Net-(IC1-PA1{slash}OSC)") (class "Default")
      (node (ref "C5") (pin "2") (pinfunction "2_2") (pintype "passive"))
      (node (ref "IC1") (pin "2") (pinfunction "PA1/OSC_2") (pintype "bidirectional"))
      (node (ref "Y1") (pin "1") (pinfunction "1_1") (pintype "passive"))
    )
    (net (code "28") (name "Net-(IC1-PA2{slash}OSCOUT)") (class "Default")
      (node (ref "C6") (pin "2") (pinfunction "2_2") (pintype "passive"))
      (node (ref "IC1") (pin "3") (pinfunction "PA2/OSCOUT_3") (pintype "bidirectional"))
      (node (ref "Y1") (pin "2") (pinfunction "2_2") (pintype "passive"))
    )
    (net (code "29") (name "Net-(IC1-VCAP)") (class "Default")
      (node (ref "C7") (pin "2") (pinfunction "2_2") (pintype "passive"))
      (node (ref "IC1") (pin "5") (pinfunction "VCAP_5") (pintype "power_in"))
    )
    (net (code "30") (name "Net-(IC2-VI)") (class "Default")
      (node (ref "IC2") (pin "3") (pinfunction "VI_3") (pintype "input"))
      (node (ref "R12") (pin "1") (pinfunction "1_1") (pintype "passive"))
    )
    (net (code "31") (name "Net-(IC3A-+IN)") (class "Default")
      (node (ref "IC3") (pin "3") (pinfunction "+IN_3") (pintype "input"))
      (node (ref "R14") (pin "2") (pinfunction "2_2") (pintype "passive"))
      (node (ref "R17") (pin "2") (pinfunction "2_2") (pintype "passive"))
      (node (ref "R18") (pin "1") (pinfunction "1_1") (pintype "passive"))
    )
    (net (code "32") (name "Net-(IC3A--IN)") (class "Default")
      (node (ref "IC3") (pin "2") (pinfunction "-IN_2") (pintype "input"))
      (node (ref "R13") (pin "2") (pinfunction "2_2") (pintype "passive"))
      (node (ref "R19") (pin "1") (pinfunction "1_1") (pintype "passive"))
      (node (ref "R20") (pin "1") (pinfunction "1_1") (pintype "passive"))
    )
    (net (code "33") (name "Net-(IC3A-OUT)") (class "Default")
      (node (ref "IC3") (pin "1") (pinfunction "OUT_1") (pintype "output"))
      (node (ref "R19") (pin "2") (pinfunction "2_2") (pintype "passive"))
      (node (ref "R20") (pin "2") (pinfunction "2_2") (pintype "passive"))
      (node (ref "R21") (pin "1") (pinfunction "1_1") (pintype "passive"))
      (node (ref "R22") (pin "1") (pinfunction "1_1") (pintype "passive"))
    )
    (net (code "34") (name "Net-(IC3B-+IN)") (class "Default")
      (node (ref "IC3") (pin "5") (pinfunction "+IN_5") (pintype "input"))
      (node (ref "R27") (pin "2") (pinfunction "2_2") (pintype "passive"))
      (node (ref "R29") (pin "2") (pinfunction "2_2") (pintype "passive"))
    )
    (net (code "35") (name "Net-(IC3B--IN)") (class "Default")
      (node (ref "C17") (pin "2") (pinfunction "2_2") (pintype "passive"))
      (node (ref "D5") (pin "C") (pinfunction "C_C") (pintype "passive"))
      (node (ref "IC3") (pin "6") (pinfunction "-IN_6") (pintype "input"))
      (node (ref "R26") (pin "1") (pinfunction "1_1") (pintype "passive"))
    )
    (net (code "36") (name "Net-(IC3B-OUT)") (class "Default")
      (node (ref "IC3") (pin "7") (pinfunction "OUT_7") (pintype "output"))
      (node (ref "R24") (pin "1") (pinfunction "1_1") (pintype "passive"))
      (node (ref "R25") (pin "2") (pinfunction "2_2") (pintype "passive"))
      (node (ref "R32") (pin "1") (pinfunction "1_1") (pintype "passive"))
    )
    (net (code "37") (name "Net-(IC3C-V+)") (class "Default")
      (node (ref "C28") (pin "2") (pinfunction "2_2") (pintype "passive"))
      (node (ref "IC3") (pin "8") (pinfunction "V+_8") (pintype "power_in"))
      (node (ref "R23") (pin "1") (pinfunction "1_1") (pintype "passive"))
      (node (ref "R31") (pin "2") (pinfunction "2_2") (pintype "passive"))
    )
    (net (code "38") (name "Net-(JP6-Pad1)") (class "Default")
      (node (ref "JP6") (pin "1") (pinfunction "1_1") (pintype "passive"))
      (node (ref "R16") (pin "1") (pinfunction "1_1") (pintype "passive"))
    )
    (net (code "39") (name "Net-(JP6-Pad2)") (class "Default")
      (node (ref "JP6") (pin "2") (pinfunction "2_2") (pintype "passive"))
      (node (ref "R15") (pin "1") (pinfunction "1_1") (pintype "passive"))
    )
    (net (code "40") (name "Net-(L1-1)") (class "Default")
      (node (ref "L1") (pin "P$1") (pinfunction "1_P$1") (pintype "passive"))
      (node (ref "Q2") (pin "3") (pinfunction "D_3") (pintype "passive"))
    )
    (net (code "41") (name "Net-(NTC1-2)") (class "Default")
      (node (ref "NTC1") (pin "P$2") (pinfunction "2_P$2") (pintype "passive"))
      (node (ref "R35") (pin "1") (pinfunction "1_1") (pintype "passive"))
      (node (ref "R36") (pin "2") (pinfunction "2_2") (pintype "passive"))
    )
    (net (code "42") (name "Net-(Q1-B)") (class "Default")
      (node (ref "C26") (pin "1") (pinfunction "1_1") (pintype "passive"))
      (node (ref "Q1") (pin "1") (pinfunction "B_1") (pintype "passive"))
      (node (ref "R1") (pin "1") (pinfunction "1_1") (pintype "passive"))
      (node (ref "R2") (pin "2") (pinfunction "2_2") (pintype "passive"))
    )
    (net (code "43") (name "Net-(Q3-B)") (class "Default")
      (node (ref "C9") (pin "2") (pinfunction "2_2") (pintype "passive"))
      (node (ref "Q3") (pin "1") (pinfunction "B_1") (pintype "passive"))
      (node (ref "R9") (pin "1") (pinfunction "1_1") (pintype "passive"))
      (node (ref "U1") (pin "3") (pinfunction "C_3") (pintype "bidirectional"))
    )
    (net (code "44") (name "Net-(Q3-C)") (class "Default")
      (node (ref "Q3") (pin "3") (pinfunction "C_3") (pintype "passive"))
      (node (ref "R8") (pin "2") (pinfunction "2_2") (pintype "passive"))
    )
    (net (code "45") (name "Net-(Q4-D)") (class "Default")
      (node (ref "D4") (pin "C") (pinfunction "C_C") (pintype "passive"))
      (node (ref "Q4") (pin "2") (pinfunction "D_2") (pintype "passive"))
    )
    (net (code "46") (name "Net-(Q4-G)") (class "Default")
      (node (ref "Q4") (pin "1") (pinfunction "G_1") (pintype "passive"))
      (node (ref "R24") (pin "2") (pinfunction "2_2") (pintype "passive"))
    )
    (net (code "47") (name "Net-(Q4-S)") (class "Default")
      (node (ref "Q4") (pin "3") (pinfunction "S_3") (pintype "passive"))
      (node (ref "R26") (pin "2") (pinfunction "2_2") (pintype "passive"))
      (node (ref "R6") (pin "P$2") (pinfunction "2_P$2") (pintype "passive"))
    )
    (net (code "48") (name "Net-(Q5-B)") (class "Default")
      (node (ref "D6") (pin "C") (pinfunction "C_C") (pintype "passive"))
      (node (ref "Q5") (pin "1") (pinfunction "B_1") (pintype "passive"))
      (node (ref "R33") (pin "2") (pinfunction "2_2") (pintype "passive"))
    )
    (net (code "49") (name "Net-(R13-Pad1)") (class "Default")
      (node (ref "R13") (pin "1") (pinfunction "1_1") (pintype "passive"))
      (node (ref "R16") (pin "2") (pinfunction "2_2") (pintype "passive"))
    )
    (net (code "50") (name "Net-(R14-Pad1)") (class "Default")
      (node (ref "R14") (pin "1") (pinfunction "1_1") (pintype "passive"))
      (node (ref "R15") (pin "2") (pinfunction "2_2") (pintype "passive"))
    )
    (net (code "51") (name "Net-(R37-Pad2)") (class "Default")
      (node (ref "R37") (pin "2") (pinfunction "2_2") (pintype "passive"))
      (node (ref "R39") (pin "1") (pinfunction "1_1") (pintype "passive"))
    )
    (net (code "52") (name "Net-(SG1-1)") (class "Default")
      (node (ref "C21") (pin "2") (pinfunction "2_2") (pintype "passive"))
      (node (ref "SG1") (pin "+") (pinfunction "1_+") (pintype "passive"))
    )
    (net (code "53") (name "Net-(U1-R)") (class "Default")
      (node (ref "C9") (pin "1") (pinfunction "1_1") (pintype "passive"))
      (node (ref "R10") (pin "1") (pinfunction "1_1") (pintype "passive"))
      (node (ref "R11") (pin "2") (pinfunction "2_2") (pintype "passive"))
      (node (ref "U1") (pin "1") (pinfunction "R_1") (pintype "bidirectional"))
    )
    (net (code "54") (name "OL_DETECT") (class "Default")
      (node (ref "IC1") (pin "19") (pinfunction "PC2/TIM1_CH2_19") (pintype "bidirectional"))
      (node (ref "Q5") (pin "3") (pinfunction "C_3") (pintype "passive"))
    )
    (net (code "55") (name "P+") (class "Default")
      (node (ref "D4") (pin "A1") (pinfunction "A1_A1") (pintype "passive"))
      (node (ref "D4") (pin "A2") (pinfunction "A2_A2") (pintype "passive"))
      (node (ref "JP7") (pin "1") (pinfunction "1_1") (pintype "passive"))
      (node (ref "R37") (pin "1") (pinfunction "1_1") (pintype "passive"))
    )
    (net (code "56") (name "PD2") (class "Default")
      (node (ref "IC1") (pin "27") (pinfunction "PD2/TIM3_CH1[TIM2_CH3]_27") (pintype "bidirectional"))
      (node (ref "R3") (pin "2") (pinfunction "2_2") (pintype "passive"))
    )
    (net (code "57") (name "RUN_P") (class "Default")
      (node (ref "C3") (pin "1") (pinfunction "1_1") (pintype "passive"))
      (node (ref "IC1") (pin "21") (pinfunction "PC4/TIM1_CH4_21") (pintype "bidirectional"))
      (node (ref "JP3") (pin "8") (pinfunction "8_8") (pintype "passive"))
    )
    (net (code "58") (name "RUN_P_DP") (class "Default")
      (node (ref "JP8") (pin "8") (pinfunction "8_8") (pintype "passive"))
      (node (ref "S1") (pin "1") (pinfunction "1_1") (pintype "passive"))
      (node (ref "S1") (pin "2") (pinfunction "2_2") (pintype "passive"))
    )
    (net (code "59") (name "RX") (class "Default")
      (node (ref "IC1") (pin "31") (pinfunction "PD6/UART2_RX_31") (pintype "bidirectional"))
      (node (ref "JP2") (pin "2") (pinfunction "2_2") (pintype "passive"))
    )
    (net (code "60") (name "SCL") (class "Default")
      (node (ref "IC1") (pin "22") (pinfunction "PC5/SPI_SCK_22") (pintype "bidirectional"))
      (node (ref "JP3") (pin "6") (pinfunction "6_6") (pintype "passive"))
    )
    (net (code "61") (name "SCL_DP") (class "Default")
      (node (ref "IC4") (pin "2") (pinfunction "SCL_2") (pintype "input"))
      (node (ref "IC5") (pin "2") (pinfunction "SCL_2") (pintype "input"))
      (node (ref "JP8") (pin "6") (pinfunction "6_6") (pintype "passive"))
    )
    (net (code "62") (name "SDA1") (class "Default")
      (node (ref "IC1") (pin "23") (pinfunction "PC6/SPI_MOSI_23") (pintype "bidirectional"))
      (node (ref "JP3") (pin "5") (pinfunction "5_5") (pintype "passive"))
    )
    (net (code "63") (name "SDA1_DP") (class "Default")
      (node (ref "IC5") (pin "3") (pinfunction "SDA_3") (pintype "bidirectional"))
      (node (ref "JP8") (pin "5") (pinfunction "5_5") (pintype "passive"))
      (node (ref "R42") (pin "2") (pinfunction "2_2") (pintype "passive"))
    )
    (net (code "64") (name "SDA2") (class "Default")
      (node (ref "IC1") (pin "24") (pinfunction "PC7/SPI_MISO_24") (pintype "bidirectional"))
      (node (ref "JP3") (pin "4") (pinfunction "4_4") (pintype "passive"))
    )
    (net (code "65") (name "SDA2_DP") (class "Default")
      (node (ref "IC4") (pin "3") (pinfunction "SDA_3") (pintype "bidirectional"))
      (node (ref "JP8") (pin "4") (pinfunction "4_4") (pintype "passive"))
      (node (ref "R41") (pin "2") (pinfunction "2_2") (pintype "passive"))
    )
    (net (code "66") (name "SWIM") (class "Default")
      (node (ref "IC1") (pin "26") (pinfunction "PD1/SWIM_26") (pintype "bidirectional"))
      (node (ref "JP1") (pin "2") (pinfunction "2_2") (pintype "passive"))
    )
    (net (code "67") (name "TEMP") (class "Default")
      (node (ref "C22") (pin "1") (pinfunction "1_1") (pintype "passive"))
      (node (ref "IC1") (pin "16") (pinfunction "PB0/AIN0[TIM1_CH1N]_16") (pintype "bidirectional"))
      (node (ref "R35") (pin "2") (pinfunction "2_2") (pintype "passive"))
    )
    (net (code "68") (name "TLI") (class "Default")
      (node (ref "IC1") (pin "32") (pinfunction "PD7/TLI[TIM1_CH4]_32") (pintype "bidirectional"))
      (node (ref "JP2") (pin "4") (pinfunction "4_4") (pintype "passive"))
    )
    (net (code "69") (name "TX") (class "Default")
      (node (ref "IC1") (pin "30") (pinfunction "PD5/UART2_TX_30") (pintype "bidirectional"))
      (node (ref "JP2") (pin "3") (pinfunction "3_3") (pintype "passive"))
    )
    (net (code "70") (name "VCC") (class "Default")
      (node (ref "C10") (pin "2") (pinfunction "2_2") (pintype "passive"))
      (node (ref "C11") (pin "1") (pinfunction "+_1") (pintype "passive"))
      (node (ref "C24") (pin "2") (pinfunction "2_2") (pintype "passive"))
      (node (ref "C8") (pin "2") (pinfunction "2_2") (pintype "passive"))
      (node (ref "IC1") (pin "6") (pinfunction "VDD_6") (pintype "power_in"))
      (node (ref "IC1") (pin "7") (pinfunction "VDDIO_1_7") (pintype "power_in"))
      (node (ref "IC1") (pin "9") (pinfunction "VDDA_9") (pintype "power_in"))
      (node (ref "JP1") (pin "1") (pinfunction "1_1") (pintype "passive"))
      (node (ref "Q3") (pin "2") (pinfunction "E_2") (pintype "passive"))
      (node (ref "R10") (pin "2") (pinfunction "2_2") (pintype "passive"))
      (node (ref "R17") (pin "1") (pinfunction "1_1") (pintype "passive"))
      (node (ref "R36") (pin "1") (pinfunction "1_1") (pintype "passive"))
      (node (ref "R38") (pin "1") (pinfunction "1_1") (pintype "passive"))
    )
    (net (code "71") (name "VCC-ISO") (class "Default")
      (node (ref "C29") (pin "1") (pinfunction "1_1") (pintype "passive"))
      (node (ref "C30") (pin "1") (pinfunction "1_1") (pintype "passive"))
      (node (ref "IC4") (pin "10") (pinfunction "VDD_10") (pintype "power_in"))
      (node (ref "IC5") (pin "10") (pinfunction "VDD_10") (pintype "power_in"))
      (node (ref "JP8") (pin "3") (pinfunction "3_3") (pintype "passive"))
      (node (ref "R41") (pin "1") (pinfunction "1_1") (pintype "passive"))
      (node (ref "R42") (pin "1") (pinfunction "1_1") (pintype "passive"))
    )
    (net (code "72") (name "VIN") (class "Default")
      (node (ref "D1") (pin "A") (pinfunction "A_A") (pintype "passive"))
      (node (ref "D2") (pin "A") (pinfunction "A_A") (pintype "passive"))
      (node (ref "JP4") (pin "PWR") (pinfunction "PWR_PWR") (pintype "bidirectional"))
    )
    (net (code "73") (name "V_INPUT") (class "Default")
      (node (ref "IC1") (pin "13") (pinfunction "PB3/AIN3[TIM1_ETR]_13") (pintype "bidirectional"))
      (node (ref "R4") (pin "2") (pinfunction "2_2") (pintype "passive"))
      (node (ref "R5") (pin "1") (pinfunction "1_1") (pintype "passive"))
    )
    (net (code "74") (name "V_LOAD") (class "Default")
      (node (ref "C23") (pin "1") (pinfunction "1_1") (pintype "passive"))
      (node (ref "IC1") (pin "15") (pinfunction "PB1/AIN1[TIM1_CH2N]_15") (pintype "bidirectional"))
      (node (ref "R38") (pin "2") (pinfunction "2_2") (pintype "passive"))
      (node (ref "R39") (pin "2") (pinfunction "2_2") (pintype "passive"))
      (node (ref "R40") (pin "2") (pinfunction "2_2") (pintype "passive"))
    )
    (net (code "75") (name "V_OK") (class "Default")
      (node (ref "IC1") (pin "28") (pinfunction "PD3/TIM2_CH2[ADC_ETR]_28") (pintype "bidirectional"))
      (node (ref "Q1") (pin "3") (pinfunction "C_3") (pintype "passive"))
    )
    (net (code "76") (name "V_SENSE") (class "Default")
      (node (ref "C16") (pin "1") (pinfunction "1_1") (pintype "passive"))
      (node (ref "IC1") (pin "14") (pinfunction "PB2/AIN2[TIM1_CH3N]_14") (pintype "bidirectional"))
      (node (ref "R21") (pin "2") (pinfunction "2_2") (pintype "passive"))
    )
    (net (code "77") (name "unconnected-(IC1-PF4{slash}AIN12-Pad8)") (class "Default")
      (node (ref "IC1") (pin "8") (pinfunction "PF4/AIN12_8") (pintype "bidirectional"))
    )
  )
)
